# ports.net
KiCad netlist of a schematic drawn in EAGLE
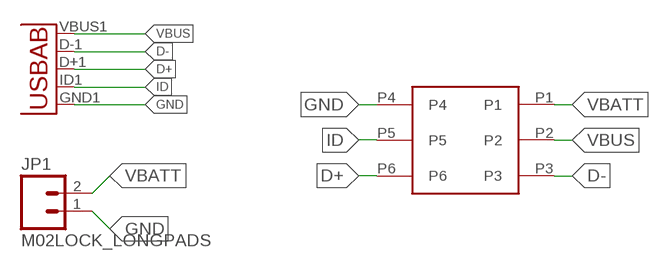
[diagram p0: schematic, sheet 1]

(export (version "E")
  (design (tool "Eeschema 10.0.6"))
  (components
    (comp (ref "JP1")
      (value "M02LOCK_LONGPADS")
      (footprint "eagle-import:1X02_LOCK_LONGPADS")
      (libsource (lib "eagle-import") (part "M02LOCK_LONGPADS"))
    )
    (comp (ref "U$1")
      (value "G125-FV20605L0P")
      (footprint "eagle-import:G125-FV20605L0P")
      (libsource (lib "eagle-import") (part "G125-FV20605L0P"))
    )
    (comp (ref "U$4")
      (value "USB-AB\"\"")
      (footprint "eagle-import:USB-AB-MICRO-SMD_V02_BOSS")
      (libsource (lib "eagle-import") (part "USB-AB{dblquote}{dblquote}"))
    )
  )
  (nets
    (net (code "1") (name "D+") (class "Default")
      (node (ref "U$1") (pin "P6") (pinfunction "P6_P6") (pintype "bidirectional"))
      (node (ref "U$4") (pin "D+1") (pinfunction "D+_D+1") (pintype "bidirectional"))
    )
    (net (code "2") (name "D-") (class "Default")
      (node (ref "U$1") (pin "P3") (pinfunction "P3_P3") (pintype "bidirectional"))
      (node (ref "U$4") (pin "D-1") (pinfunction "D-_D-1") (pintype "bidirectional"))
    )
    (net (code "3") (name "GND") (class "Default")
      (node (ref "JP1") (pin "1") (pinfunction "1_1") (pintype "passive"))
      (node (ref "U$1") (pin "P4") (pinfunction "P4_P4") (pintype "bidirectional"))
      (node (ref "U$4") (pin "GND1") (pinfunction "GND_GND1") (pintype "bidirectional"))
    )
    (net (code "4") (name "ID") (class "Default")
      (node (ref "U$1") (pin "P5") (pinfunction "P5_P5") (pintype "bidirectional"))
      (node (ref "U$4") (pin "ID1") (pinfunction "USBID_ID1") (pintype "bidirectional"))
    )
    (net (code "5") (name "VBATT") (class "Default")
      (node (ref "JP1") (pin "2") (pinfunction "2_2") (pintype "passive"))
      (node (ref "U$1") (pin "P1") (pinfunction "P1_P1") (pintype "bidirectional"))
    )
    (net (code "6") (name "VBUS") (class "Default")
      (node (ref "U$1") (pin "P2") (pinfunction "P2_P2") (pintype "bidirectional"))
      (node (ref "U$4") (pin "VBUS1") (pinfunction "VBUS_VBUS1") (pintype "bidirectional"))
    )
  )
)
